# tb6560openhw.net
KiCad netlist of a schematic drawn in EAGLE
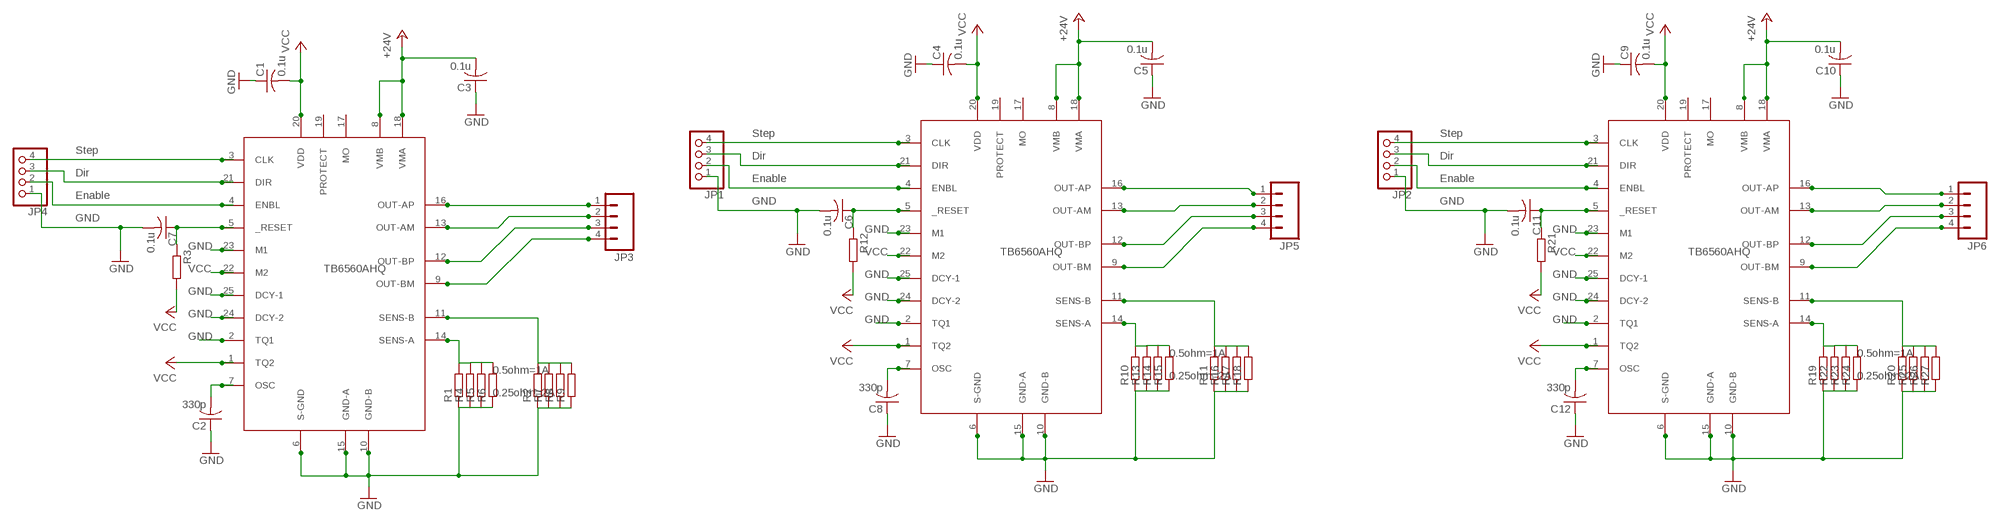
[diagram p0: schematic, sheet 1]

(export (version "E")
  (design (tool "Eeschema 10.0.6"))
  (components
    (comp (ref "C1")
      (value "0.1u")
      (footprint "eagle-import:C1206K")
      (libsource (lib "eagle-import") (part "C-USC1206K"))
    )
    (comp (ref "C2")
      (value "330p")
      (footprint "eagle-import:C1206K")
      (libsource (lib "eagle-import") (part "C-USC1206K"))
    )
    (comp (ref "C3")
      (value "0.1u")
      (footprint "eagle-import:C1206K")
      (libsource (lib "eagle-import") (part "C-USC1206K"))
    )
    (comp (ref "C4")
      (value "0.1u")
      (footprint "eagle-import:C1206K")
      (libsource (lib "eagle-import") (part "C-USC1206K"))
    )
    (comp (ref "C5")
      (value "0.1u")
      (footprint "eagle-import:C1206K")
      (libsource (lib "eagle-import") (part "C-USC1206K"))
    )
    (comp (ref "C6")
      (value "0.1u")
      (footprint "eagle-import:C1206K")
      (libsource (lib "eagle-import") (part "C-USC1206K"))
    )
    (comp (ref "C7")
      (value "0.1u")
      (footprint "eagle-import:C1206K")
      (libsource (lib "eagle-import") (part "C-USC1206K"))
    )
    (comp (ref "C8")
      (value "330p")
      (footprint "eagle-import:C1206K")
      (libsource (lib "eagle-import") (part "C-USC1206K"))
    )
    (comp (ref "C9")
      (value "0.1u")
      (footprint "eagle-import:C1206K")
      (libsource (lib "eagle-import") (part "C-USC1206K"))
    )
    (comp (ref "C10")
      (value "0.1u")
      (footprint "eagle-import:C1206K")
      (libsource (lib "eagle-import") (part "C-USC1206K"))
    )
    (comp (ref "C11")
      (value "0.1u")
      (footprint "eagle-import:C1206K")
      (libsource (lib "eagle-import") (part "C-USC1206K"))
    )
    (comp (ref "C12")
      (value "330p")
      (footprint "eagle-import:C1206K")
      (libsource (lib "eagle-import") (part "C-USC1206K"))
    )
    (comp (ref "JP1")
      (value "PINHD-1X4")
      (footprint "eagle-import:1X04")
      (libsource (lib "eagle-import") (part "PINHD-1X4"))
    )
    (comp (ref "JP2")
      (value "PINHD-1X4")
      (footprint "eagle-import:1X04")
      (libsource (lib "eagle-import") (part "PINHD-1X4"))
    )
    (comp (ref "JP3")
      (value "M04SCREW")
      (footprint "eagle-import:SCREWTERMINAL-3.5MM-4")
      (libsource (lib "eagle-import") (part "M04SCREW"))
    )
    (comp (ref "JP4")
      (value "PINHD-1X4")
      (footprint "eagle-import:1X04")
      (libsource (lib "eagle-import") (part "PINHD-1X4"))
    )
    (comp (ref "JP5")
      (value "M04SCREW")
      (footprint "eagle-import:SCREWTERMINAL-3.5MM-4")
      (libsource (lib "eagle-import") (part "M04SCREW"))
    )
    (comp (ref "JP6")
      (value "M04SCREW")
      (footprint "eagle-import:SCREWTERMINAL-3.5MM-4")
      (libsource (lib "eagle-import") (part "M04SCREW"))
    )
    (comp (ref "R1")
      (value "R-EU_0411/3V")
      (footprint "eagle-import:0411V")
      (libsource (lib "eagle-import") (part "R-EU_0411/3V"))
    )
    (comp (ref "R2")
      (value "R-EU_0411/3V")
      (footprint "eagle-import:0411V")
      (libsource (lib "eagle-import") (part "R-EU_0411/3V"))
    )
    (comp (ref "R3")
      (value "R-EU_0207/10")
      (footprint "eagle-import:0207_10")
      (libsource (lib "eagle-import") (part "rcl_R-EU_0207/10"))
    )
    (comp (ref "R4")
      (value "R-EU_0411/3V")
      (footprint "eagle-import:0411V")
      (libsource (lib "eagle-import") (part "R-EU_0411/3V"))
    )
    (comp (ref "R5")
      (value "R-EU_0411/3V")
      (footprint "eagle-import:0411V")
      (libsource (lib "eagle-import") (part "R-EU_0411/3V"))
    )
    (comp (ref "R6")
      (value "R-EU_0411/3V")
      (footprint "eagle-import:0411V")
      (libsource (lib "eagle-import") (part "R-EU_0411/3V"))
    )
    (comp (ref "R7")
      (value "R-EU_0411/3V")
      (footprint "eagle-import:0411V")
      (libsource (lib "eagle-import") (part "R-EU_0411/3V"))
    )
    (comp (ref "R8")
      (value "R-EU_0411/3V")
      (footprint "eagle-import:0411V")
      (libsource (lib "eagle-import") (part "R-EU_0411/3V"))
    )
    (comp (ref "R9")
      (value "R-EU_0411/3V")
      (footprint "eagle-import:0411V")
      (libsource (lib "eagle-import") (part "R-EU_0411/3V"))
    )
    (comp (ref "R10")
      (value "R-EU_0411/3V")
      (footprint "eagle-import:0411V")
      (libsource (lib "eagle-import") (part "R-EU_0411/3V"))
    )
    (comp (ref "R11")
      (value "R-EU_0411/3V")
      (footprint "eagle-import:0411V")
      (libsource (lib "eagle-import") (part "R-EU_0411/3V"))
    )
    (comp (ref "R12")
      (value "R-EU_0207/10")
      (footprint "eagle-import:0207_10")
      (libsource (lib "eagle-import") (part "rcl_R-EU_0207/10"))
    )
    (comp (ref "R13")
      (value "R-EU_0411/3V")
      (footprint "eagle-import:0411V")
      (libsource (lib "eagle-import") (part "R-EU_0411/3V"))
    )
    (comp (ref "R14")
      (value "R-EU_0411/3V")
      (footprint "eagle-import:0411V")
      (libsource (lib "eagle-import") (part "R-EU_0411/3V"))
    )
    (comp (ref "R15")
      (value "R-EU_0411/3V")
      (footprint "eagle-import:0411V")
      (libsource (lib "eagle-import") (part "R-EU_0411/3V"))
    )
    (comp (ref "R16")
      (value "R-EU_0411/3V")
      (footprint "eagle-import:0411V")
      (libsource (lib "eagle-import") (part "R-EU_0411/3V"))
    )
    (comp (ref "R17")
      (value "R-EU_0411/3V")
      (footprint "eagle-import:0411V")
      (libsource (lib "eagle-import") (part "R-EU_0411/3V"))
    )
    (comp (ref "R18")
      (value "R-EU_0411/3V")
      (footprint "eagle-import:0411V")
      (libsource (lib "eagle-import") (part "R-EU_0411/3V"))
    )
    (comp (ref "R19")
      (value "R-EU_0411/3V")
      (footprint "eagle-import:0411V")
      (libsource (lib "eagle-import") (part "R-EU_0411/3V"))
    )
    (comp (ref "R20")
      (value "R-EU_0411/3V")
      (footprint "eagle-import:0411V")
      (libsource (lib "eagle-import") (part "R-EU_0411/3V"))
    )
    (comp (ref "R21")
      (value "R-EU_0207/10")
      (footprint "eagle-import:0207_10")
      (libsource (lib "eagle-import") (part "rcl_R-EU_0207/10"))
    )
    (comp (ref "R22")
      (value "R-EU_0411/3V")
      (footprint "eagle-import:0411V")
      (libsource (lib "eagle-import") (part "R-EU_0411/3V"))
    )
    (comp (ref "R23")
      (value "R-EU_0411/3V")
      (footprint "eagle-import:0411V")
      (libsource (lib "eagle-import") (part "R-EU_0411/3V"))
    )
    (comp (ref "R24")
      (value "R-EU_0411/3V")
      (footprint "eagle-import:0411V")
      (libsource (lib "eagle-import") (part "R-EU_0411/3V"))
    )
    (comp (ref "R25")
      (value "R-EU_0411/3V")
      (footprint "eagle-import:0411V")
      (libsource (lib "eagle-import") (part "R-EU_0411/3V"))
    )
    (comp (ref "R26")
      (value "R-EU_0411/3V")
      (footprint "eagle-import:0411V")
      (libsource (lib "eagle-import") (part "R-EU_0411/3V"))
    )
    (comp (ref "R27")
      (value "R-EU_0411/3V")
      (footprint "eagle-import:0411V")
      (libsource (lib "eagle-import") (part "R-EU_0411/3V"))
    )
    (comp (ref "U$1")
      (value "TB6560-H")
      (footprint "eagle-import:ZIP25-H")
      (libsource (lib "eagle-import") (part "TB6560-H"))
    )
    (comp (ref "U$2")
      (value "TB6560-H")
      (footprint "eagle-import:ZIP25-H")
      (libsource (lib "eagle-import") (part "TB6560-H"))
    )
    (comp (ref "U$3")
      (value "TB6560-H")
      (footprint "eagle-import:ZIP25-H")
      (libsource (lib "eagle-import") (part "TB6560-H"))
    )
  )
  (nets
    (net (code "1") (name "+24V") (class "Default")
      (node (ref "C10") (pin "2") (pinfunction "2_2") (pintype "passive"))
      (node (ref "C3") (pin "2") (pinfunction "2_2") (pintype "passive"))
      (node (ref "C5") (pin "2") (pinfunction "2_2") (pintype "passive"))
      (node (ref "U$1") (pin "18") (pinfunction "VMA_18") (pintype "bidirectional"))
      (node (ref "U$1") (pin "8") (pinfunction "VMB_8") (pintype "bidirectional"))
      (node (ref "U$2") (pin "18") (pinfunction "VMA_18") (pintype "bidirectional"))
      (node (ref "U$2") (pin "8") (pinfunction "VMB_8") (pintype "bidirectional"))
      (node (ref "U$3") (pin "18") (pinfunction "VMA_18") (pintype "bidirectional"))
      (node (ref "U$3") (pin "8") (pinfunction "VMB_8") (pintype "bidirectional"))
    )
    (net (code "2") (name "/ENABLE") (class "Default")
      (node (ref "JP1") (pin "2") (pinfunction "2_2") (pintype "passive"))
      (node (ref "JP2") (pin "2") (pinfunction "2_2") (pintype "passive"))
      (node (ref "JP4") (pin "2") (pinfunction "2_2") (pintype "passive"))
      (node (ref "U$1") (pin "4") (pinfunction "ENBL_4") (pintype "bidirectional"))
      (node (ref "U$2") (pin "4") (pinfunction "ENBL_4") (pintype "bidirectional"))
      (node (ref "U$3") (pin "4") (pinfunction "ENBL_4") (pintype "bidirectional"))
    )
    (net (code "3") (name "GND") (class "Default")
      (node (ref "C1") (pin "1") (pinfunction "1_1") (pintype "passive"))
      (node (ref "C10") (pin "1") (pinfunction "1_1") (pintype "passive"))
      (node (ref "C11") (pin "2") (pinfunction "2_2") (pintype "passive"))
      (node (ref "C12") (pin "1") (pinfunction "1_1") (pintype "passive"))
      (node (ref "C2") (pin "1") (pinfunction "1_1") (pintype "passive"))
      (node (ref "C3") (pin "1") (pinfunction "1_1") (pintype "passive"))
      (node (ref "C4") (pin "1") (pinfunction "1_1") (pintype "passive"))
      (node (ref "C5") (pin "1") (pinfunction "1_1") (pintype "passive"))
      (node (ref "C6") (pin "2") (pinfunction "2_2") (pintype "passive"))
      (node (ref "C7") (pin "2") (pinfunction "2_2") (pintype "passive"))
      (node (ref "C8") (pin "1") (pinfunction "1_1") (pintype "passive"))
      (node (ref "C9") (pin "1") (pinfunction "1_1") (pintype "passive"))
      (node (ref "JP1") (pin "1") (pinfunction "1_1") (pintype "passive"))
      (node (ref "JP2") (pin "1") (pinfunction "1_1") (pintype "passive"))
      (node (ref "JP4") (pin "1") (pinfunction "1_1") (pintype "passive"))
      (node (ref "R1") (pin "1") (pinfunction "1_1") (pintype "passive"))
      (node (ref "R10") (pin "1") (pinfunction "1_1") (pintype "passive"))
      (node (ref "R11") (pin "1") (pinfunction "1_1") (pintype "passive"))
      (node (ref "R13") (pin "1") (pinfunction "1_1") (pintype "passive"))
      (node (ref "R14") (pin "1") (pinfunction "1_1") (pintype "passive"))
      (node (ref "R15") (pin "1") (pinfunction "1_1") (pintype "passive"))
      (node (ref "R16") (pin "1") (pinfunction "1_1") (pintype "passive"))
      (node (ref "R17") (pin "1") (pinfunction "1_1") (pintype "passive"))
      (node (ref "R18") (pin "1") (pinfunction "1_1") (pintype "passive"))
      (node (ref "R19") (pin "1") (pinfunction "1_1") (pintype "passive"))
      (node (ref "R2") (pin "1") (pinfunction "1_1") (pintype "passive"))
      (node (ref "R20") (pin "1") (pinfunction "1_1") (pintype "passive"))
      (node (ref "R22") (pin "1") (pinfunction "1_1") (pintype "passive"))
      (node (ref "R23") (pin "1") (pinfunction "1_1") (pintype "passive"))
      (node (ref "R24") (pin "1") (pinfunction "1_1") (pintype "passive"))
      (node (ref "R25") (pin "1") (pinfunction "1_1") (pintype "passive"))
      (node (ref "R26") (pin "1") (pinfunction "1_1") (pintype "passive"))
      (node (ref "R27") (pin "1") (pinfunction "1_1") (pintype "passive"))
      (node (ref "R4") (pin "1") (pinfunction "1_1") (pintype "passive"))
      (node (ref "R5") (pin "1") (pinfunction "1_1") (pintype "passive"))
      (node (ref "R6") (pin "1") (pinfunction "1_1") (pintype "passive"))
      (node (ref "R7") (pin "1") (pinfunction "1_1") (pintype "passive"))
      (node (ref "R8") (pin "1") (pinfunction "1_1") (pintype "passive"))
      (node (ref "R9") (pin "1") (pinfunction "1_1") (pintype "passive"))
      (node (ref "U$1") (pin "10") (pinfunction "GND-B_10") (pintype "bidirectional"))
      (node (ref "U$1") (pin "15") (pinfunction "GND-A_15") (pintype "bidirectional"))
      (node (ref "U$1") (pin "2") (pinfunction "TQ1_2") (pintype "bidirectional"))
      (node (ref "U$1") (pin "23") (pinfunction "M1_23") (pintype "bidirectional"))
      (node (ref "U$1") (pin "24") (pinfunction "DCY-2_24") (pintype "bidirectional"))
      (node (ref "U$1") (pin "25") (pinfunction "DCY-1_25") (pintype "bidirectional"))
      (node (ref "U$1") (pin "6") (pinfunction "S-GND_6") (pintype "bidirectional"))
      (node (ref "U$2") (pin "10") (pinfunction "GND-B_10") (pintype "bidirectional"))
      (node (ref "U$2") (pin "15") (pinfunction "GND-A_15") (pintype "bidirectional"))
      (node (ref "U$2") (pin "2") (pinfunction "TQ1_2") (pintype "bidirectional"))
      (node (ref "U$2") (pin "23") (pinfunction "M1_23") (pintype "bidirectional"))
      (node (ref "U$2") (pin "24") (pinfunction "DCY-2_24") (pintype "bidirectional"))
      (node (ref "U$2") (pin "25") (pinfunction "DCY-1_25") (pintype "bidirectional"))
      (node (ref "U$2") (pin "6") (pinfunction "S-GND_6") (pintype "bidirectional"))
      (node (ref "U$3") (pin "10") (pinfunction "GND-B_10") (pintype "bidirectional"))
      (node (ref "U$3") (pin "15") (pinfunction "GND-A_15") (pintype "bidirectional"))
      (node (ref "U$3") (pin "2") (pinfunction "TQ1_2") (pintype "bidirectional"))
      (node (ref "U$3") (pin "23") (pinfunction "M1_23") (pintype "bidirectional"))
      (node (ref "U$3") (pin "24") (pinfunction "DCY-2_24") (pintype "bidirectional"))
      (node (ref "U$3") (pin "25") (pinfunction "DCY-1_25") (pintype "bidirectional"))
      (node (ref "U$3") (pin "6") (pinfunction "S-GND_6") (pintype "bidirectional"))
    )
    (net (code "4") (name "Net-(U$1-CLK)") (class "Default")
      (node (ref "JP4") (pin "4") (pinfunction "4_4") (pintype "passive"))
      (node (ref "U$1") (pin "3") (pinfunction "CLK_3") (pintype "bidirectional"))
    )
    (net (code "5") (name "Net-(U$1-DIR)") (class "Default")
      (node (ref "JP4") (pin "3") (pinfunction "3_3") (pintype "passive"))
      (node (ref "U$1") (pin "21") (pinfunction "DIR_21") (pintype "bidirectional"))
    )
    (net (code "6") (name "Net-(U$1-OSC)") (class "Default")
      (node (ref "C2") (pin "2") (pinfunction "2_2") (pintype "passive"))
      (node (ref "U$1") (pin "7") (pinfunction "OSC_7") (pintype "bidirectional"))
    )
    (net (code "7") (name "Net-(U$1-OUT-AM)") (class "Default")
      (node (ref "JP3") (pin "2") (pinfunction "2_2") (pintype "passive"))
      (node (ref "U$1") (pin "13") (pinfunction "OUT-AM_13") (pintype "output"))
    )
    (net (code "8") (name "Net-(U$1-OUT-AP)") (class "Default")
      (node (ref "JP3") (pin "1") (pinfunction "1_1") (pintype "passive"))
      (node (ref "U$1") (pin "16") (pinfunction "OUT-AP_16") (pintype "output"))
    )
    (net (code "9") (name "Net-(U$1-OUT-BM)") (class "Default")
      (node (ref "JP3") (pin "4") (pinfunction "4_4") (pintype "passive"))
      (node (ref "U$1") (pin "9") (pinfunction "OUT-BM_9") (pintype "output"))
    )
    (net (code "10") (name "Net-(U$1-OUT-BP)") (class "Default")
      (node (ref "JP3") (pin "3") (pinfunction "3_3") (pintype "passive"))
      (node (ref "U$1") (pin "12") (pinfunction "OUT-BP_12") (pintype "output"))
    )
    (net (code "11") (name "Net-(U$1-SENS-A)") (class "Default")
      (node (ref "R1") (pin "2") (pinfunction "2_2") (pintype "passive"))
      (node (ref "R4") (pin "2") (pinfunction "2_2") (pintype "passive"))
      (node (ref "R5") (pin "2") (pinfunction "2_2") (pintype "passive"))
      (node (ref "R6") (pin "2") (pinfunction "2_2") (pintype "passive"))
      (node (ref "U$1") (pin "14") (pinfunction "SENS-A_14") (pintype "bidirectional"))
    )
    (net (code "12") (name "Net-(U$1-SENS-B)") (class "Default")
      (node (ref "R2") (pin "2") (pinfunction "2_2") (pintype "passive"))
      (node (ref "R7") (pin "2") (pinfunction "2_2") (pintype "passive"))
      (node (ref "R8") (pin "2") (pinfunction "2_2") (pintype "passive"))
      (node (ref "R9") (pin "2") (pinfunction "2_2") (pintype "passive"))
      (node (ref "U$1") (pin "11") (pinfunction "SENS-B_11") (pintype "bidirectional"))
    )
    (net (code "13") (name "Net-(U$1-_RESET)") (class "Default")
      (node (ref "C7") (pin "1") (pinfunction "1_1") (pintype "passive"))
      (node (ref "R3") (pin "1") (pinfunction "1_1") (pintype "passive"))
      (node (ref "U$1") (pin "5") (pinfunction "_RESET_5") (pintype "bidirectional"))
    )
    (net (code "14") (name "Net-(U$2-CLK)") (class "Default")
      (node (ref "JP1") (pin "4") (pinfunction "4_4") (pintype "passive"))
      (node (ref "U$2") (pin "3") (pinfunction "CLK_3") (pintype "bidirectional"))
    )
    (net (code "15") (name "Net-(U$2-DIR)") (class "Default")
      (node (ref "JP1") (pin "3") (pinfunction "3_3") (pintype "passive"))
      (node (ref "U$2") (pin "21") (pinfunction "DIR_21") (pintype "bidirectional"))
    )
    (net (code "16") (name "Net-(U$2-OSC)") (class "Default")
      (node (ref "C8") (pin "2") (pinfunction "2_2") (pintype "passive"))
      (node (ref "U$2") (pin "7") (pinfunction "OSC_7") (pintype "bidirectional"))
    )
    (net (code "17") (name "Net-(U$2-OUT-AM)") (class "Default")
      (node (ref "JP5") (pin "2") (pinfunction "2_2") (pintype "passive"))
      (node (ref "U$2") (pin "13") (pinfunction "OUT-AM_13") (pintype "output"))
    )
    (net (code "18") (name "Net-(U$2-OUT-AP)") (class "Default")
      (node (ref "JP5") (pin "1") (pinfunction "1_1") (pintype "passive"))
      (node (ref "U$2") (pin "16") (pinfunction "OUT-AP_16") (pintype "output"))
    )
    (net (code "19") (name "Net-(U$2-OUT-BM)") (class "Default")
      (node (ref "JP5") (pin "4") (pinfunction "4_4") (pintype "passive"))
      (node (ref "U$2") (pin "9") (pinfunction "OUT-BM_9") (pintype "output"))
    )
    (net (code "20") (name "Net-(U$2-OUT-BP)") (class "Default")
      (node (ref "JP5") (pin "3") (pinfunction "3_3") (pintype "passive"))
      (node (ref "U$2") (pin "12") (pinfunction "OUT-BP_12") (pintype "output"))
    )
    (net (code "21") (name "Net-(U$2-SENS-A)") (class "Default")
      (node (ref "R10") (pin "2") (pinfunction "2_2") (pintype "passive"))
      (node (ref "R13") (pin "2") (pinfunction "2_2") (pintype "passive"))
      (node (ref "R14") (pin "2") (pinfunction "2_2") (pintype "passive"))
      (node (ref "R15") (pin "2") (pinfunction "2_2") (pintype "passive"))
      (node (ref "U$2") (pin "14") (pinfunction "SENS-A_14") (pintype "bidirectional"))
    )
    (net (code "22") (name "Net-(U$2-SENS-B)") (class "Default")
      (node (ref "R11") (pin "2") (pinfunction "2_2") (pintype "passive"))
      (node (ref "R16") (pin "2") (pinfunction "2_2") (pintype "passive"))
      (node (ref "R17") (pin "2") (pinfunction "2_2") (pintype "passive"))
      (node (ref "R18") (pin "2") (pinfunction "2_2") (pintype "passive"))
      (node (ref "U$2") (pin "11") (pinfunction "SENS-B_11") (pintype "bidirectional"))
    )
    (net (code "23") (name "Net-(U$2-_RESET)") (class "Default")
      (node (ref "C6") (pin "1") (pinfunction "1_1") (pintype "passive"))
      (node (ref "R12") (pin "1") (pinfunction "1_1") (pintype "passive"))
      (node (ref "U$2") (pin "5") (pinfunction "_RESET_5") (pintype "bidirectional"))
    )
    (net (code "24") (name "Net-(U$3-CLK)") (class "Default")
      (node (ref "JP2") (pin "4") (pinfunction "4_4") (pintype "passive"))
      (node (ref "U$3") (pin "3") (pinfunction "CLK_3") (pintype "bidirectional"))
    )
    (net (code "25") (name "Net-(U$3-DIR)") (class "Default")
      (node (ref "JP2") (pin "3") (pinfunction "3_3") (pintype "passive"))
      (node (ref "U$3") (pin "21") (pinfunction "DIR_21") (pintype "bidirectional"))
    )
    (net (code "26") (name "Net-(U$3-OSC)") (class "Default")
      (node (ref "C12") (pin "2") (pinfunction "2_2") (pintype "passive"))
      (node (ref "U$3") (pin "7") (pinfunction "OSC_7") (pintype "bidirectional"))
    )
    (net (code "27") (name "Net-(U$3-OUT-AM)") (class "Default")
      (node (ref "JP6") (pin "2") (pinfunction "2_2") (pintype "passive"))
      (node (ref "U$3") (pin "13") (pinfunction "OUT-AM_13") (pintype "output"))
    )
    (net (code "28") (name "Net-(U$3-OUT-AP)") (class "Default")
      (node (ref "JP6") (pin "1") (pinfunction "1_1") (pintype "passive"))
      (node (ref "U$3") (pin "16") (pinfunction "OUT-AP_16") (pintype "output"))
    )
    (net (code "29") (name "Net-(U$3-OUT-BM)") (class "Default")
      (node (ref "JP6") (pin "4") (pinfunction "4_4") (pintype "passive"))
      (node (ref "U$3") (pin "9") (pinfunction "OUT-BM_9") (pintype "output"))
    )
    (net (code "30") (name "Net-(U$3-OUT-BP)") (class "Default")
      (node (ref "JP6") (pin "3") (pinfunction "3_3") (pintype "passive"))
      (node (ref "U$3") (pin "12") (pinfunction "OUT-BP_12") (pintype "output"))
    )
    (net (code "31") (name "Net-(U$3-SENS-A)") (class "Default")
      (node (ref "R19") (pin "2") (pinfunction "2_2") (pintype "passive"))
      (node (ref "R22") (pin "2") (pinfunction "2_2") (pintype "passive"))
      (node (ref "R23") (pin "2") (pinfunction "2_2") (pintype "passive"))
      (node (ref "R24") (pin "2") (pinfunction "2_2") (pintype "passive"))
      (node (ref "U$3") (pin "14") (pinfunction "SENS-A_14") (pintype "bidirectional"))
    )
    (net (code "32") (name "Net-(U$3-SENS-B)") (class "Default")
      (node (ref "R20") (pin "2") (pinfunction "2_2") (pintype "passive"))
      (node (ref "R25") (pin "2") (pinfunction "2_2") (pintype "passive"))
      (node (ref "R26") (pin "2") (pinfunction "2_2") (pintype "passive"))
      (node (ref "R27") (pin "2") (pinfunction "2_2") (pintype "passive"))
      (node (ref "U$3") (pin "11") (pinfunction "SENS-B_11") (pintype "bidirectional"))
    )
    (net (code "33") (name "Net-(U$3-_RESET)") (class "Default")
      (node (ref "C11") (pin "1") (pinfunction "1_1") (pintype "passive"))
      (node (ref "R21") (pin "1") (pinfunction "1_1") (pintype "passive"))
      (node (ref "U$3") (pin "5") (pinfunction "_RESET_5") (pintype "bidirectional"))
    )
    (net (code "34") (name "VCC") (class "Default")
      (node (ref "C1") (pin "2") (pinfunction "2_2") (pintype "passive"))
      (node (ref "C4") (pin "2") (pinfunction "2_2") (pintype "passive"))
      (node (ref "C9") (pin "2") (pinfunction "2_2") (pintype "passive"))
      (node (ref "R12") (pin "2") (pinfunction "2_2") (pintype "passive"))
      (node (ref "R21") (pin "2") (pinfunction "2_2") (pintype "passive"))
      (node (ref "R3") (pin "2") (pinfunction "2_2") (pintype "passive"))
      (node (ref "U$1") (pin "1") (pinfunction "TQ2_1") (pintype "bidirectional"))
      (node (ref "U$1") (pin "20") (pinfunction "VDD_20") (pintype "bidirectional"))
      (node (ref "U$1") (pin "22") (pinfunction "M2_22") (pintype "bidirectional"))
      (node (ref "U$2") (pin "1") (pinfunction "TQ2_1") (pintype "bidirectional"))
      (node (ref "U$2") (pin "20") (pinfunction "VDD_20") (pintype "bidirectional"))
      (node (ref "U$2") (pin "22") (pinfunction "M2_22") (pintype "bidirectional"))
      (node (ref "U$3") (pin "1") (pinfunction "TQ2_1") (pintype "bidirectional"))
      (node (ref "U$3") (pin "20") (pinfunction "VDD_20") (pintype "bidirectional"))
      (node (ref "U$3") (pin "22") (pinfunction "M2_22") (pintype "bidirectional"))
    )
    (net (code "35") (name "unconnected-(U$1-MO-Pad17)") (class "Default")
      (node (ref "U$1") (pin "17") (pinfunction "MO_17") (pintype "bidirectional"))
    )
    (net (code "36") (name "unconnected-(U$1-PROTECT-Pad19)") (class "Default")
      (node (ref "U$1") (pin "19") (pinfunction "PROTECT_19") (pintype "bidirectional"))
    )
    (net (code "37") (name "unconnected-(U$2-MO-Pad17)") (class "Default")
      (node (ref "U$2") (pin "17") (pinfunction "MO_17") (pintype "bidirectional"))
    )
    (net (code "38") (name "unconnected-(U$2-PROTECT-Pad19)") (class "Default")
      (node (ref "U$2") (pin "19") (pinfunction "PROTECT_19") (pintype "bidirectional"))
    )
    (net (code "39") (name "unconnected-(U$3-MO-Pad17)") (class "Default")
      (node (ref "U$3") (pin "17") (pinfunction "MO_17") (pintype "bidirectional"))
    )
    (net (code "40") (name "unconnected-(U$3-PROTECT-Pad19)") (class "Default")
      (node (ref "U$3") (pin "19") (pinfunction "PROTECT_19") (pintype "bidirectional"))
    )
  )
)
